# Week_9_8.net
KiCad netlist of a schematic drawn in EAGLE
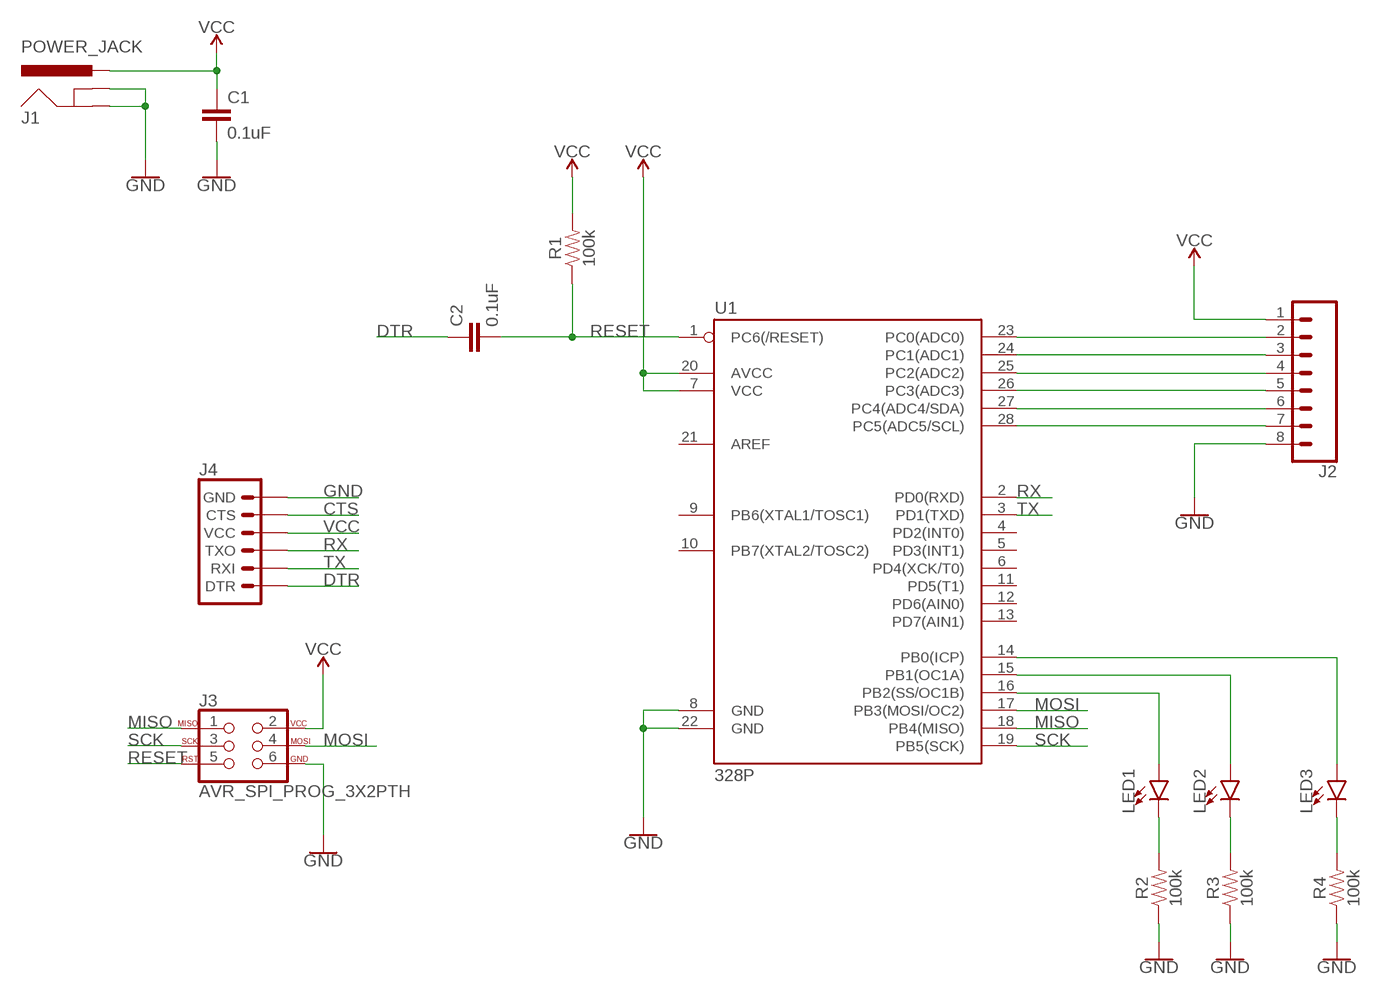
[diagram p0: schematic, sheet 1]

(export (version "E")
  (design (tool "Eeschema 10.0.6"))
  (components
    (comp (ref "C1")
      (value "0.1uF")
      (footprint "eagle-import:CAP-PTH-SMALL-KIT")
      (libsource (lib "eagle-import") (part "0.1UF-KIT-EZ-50V-20%"))
    )
    (comp (ref "C2")
      (value "0.1uF")
      (footprint "eagle-import:CAP-PTH-SMALL-KIT")
      (libsource (lib "eagle-import") (part "0.1UF-KIT-EZ-50V-20%"))
    )
    (comp (ref "J1")
      (value "POWER_JACK")
      (footprint "eagle-import:POWER_JACK_PTH")
      (libsource (lib "eagle-import") (part "POWER_JACK"))
    )
    (comp (ref "J2")
      (value "CONN_08\"")
      (footprint "eagle-import:1X08")
      (libsource (lib "eagle-import") (part "CONN_08{dblquote}"))
    )
    (comp (ref "J3")
      (value "AVR_SPI_PROG_3X2PTH")
      (footprint "eagle-import:2X3")
      (libsource (lib "eagle-import") (part "AVR_SPI_PROG_3X2PTH"))
    )
    (comp (ref "J4")
      (value "6_PIN_SERIAL_TARGET")
      (footprint "eagle-import:1X06")
      (libsource (lib "eagle-import") (part "6_PIN_SERIAL_TARGET"))
    )
    (comp (ref "LED1")
      (value "LED5MM")
      (footprint "eagle-import:LED_5MM")
      (libsource (lib "eagle-import") (part "LED5MM"))
    )
    (comp (ref "LED2")
      (value "LED5MM")
      (footprint "eagle-import:LED_5MM")
      (libsource (lib "eagle-import") (part "LED5MM"))
    )
    (comp (ref "LED3")
      (value "LED5MM")
      (footprint "eagle-import:LED_5MM")
      (libsource (lib "eagle-import") (part "LED5MM"))
    )
    (comp (ref "R1")
      (value "100k")
      (footprint "eagle-import:AXIAL-0.3")
      (libsource (lib "eagle-import") (part "100KOHM-HORIZ-1/4W-1%"))
    )
    (comp (ref "R2")
      (value "100k")
      (footprint "eagle-import:AXIAL-0.3")
      (libsource (lib "eagle-import") (part "100KOHM-HORIZ-1/4W-1%"))
    )
    (comp (ref "R3")
      (value "100k")
      (footprint "eagle-import:AXIAL-0.3")
      (libsource (lib "eagle-import") (part "100KOHM-HORIZ-1/4W-1%"))
    )
    (comp (ref "R4")
      (value "100k")
      (footprint "eagle-import:AXIAL-0.3")
      (libsource (lib "eagle-import") (part "100KOHM-HORIZ-1/4W-1%"))
    )
    (comp (ref "U1")
      (value "328P")
      (footprint "eagle-import:DIP28")
      (libsource (lib "eagle-import") (part "ATMEGA328P_PDIP"))
    )
  )
  (nets
    (net (code "1") (name "/CTS") (class "Default")
      (node (ref "J4") (pin "5") (pinfunction "CTS_5") (pintype "passive"))
    )
    (net (code "2") (name "/DTR") (class "Default")
      (node (ref "C2") (pin "1") (pinfunction "1_1") (pintype "passive"))
      (node (ref "J4") (pin "1") (pinfunction "DTR_1") (pintype "passive"))
    )
    (net (code "3") (name "/MISO") (class "Default")
      (node (ref "J3") (pin "1") (pinfunction "1_1") (pintype "passive"))
      (node (ref "U1") (pin "18") (pinfunction "PB4(MISO)_18") (pintype "bidirectional"))
    )
    (net (code "4") (name "/MOSI") (class "Default")
      (node (ref "J3") (pin "4") (pinfunction "4_4") (pintype "passive"))
      (node (ref "U1") (pin "17") (pinfunction "PB3(MOSI/OC2)_17") (pintype "bidirectional"))
    )
    (net (code "5") (name "/RESET") (class "Default")
      (node (ref "C2") (pin "2") (pinfunction "2_2") (pintype "passive"))
      (node (ref "J3") (pin "5") (pinfunction "5_5") (pintype "passive"))
      (node (ref "R1") (pin "P$1") (pinfunction "1_P$1") (pintype "passive"))
      (node (ref "U1") (pin "1") (pinfunction "PC6(/RESET)_1") (pintype "bidirectional"))
    )
    (net (code "6") (name "/RX") (class "Default")
      (node (ref "J4") (pin "3") (pinfunction "TXO_3") (pintype "passive"))
      (node (ref "U1") (pin "2") (pinfunction "PD0(RXD)_2") (pintype "bidirectional"))
    )
    (net (code "7") (name "/SCK") (class "Default")
      (node (ref "J3") (pin "3") (pinfunction "3_3") (pintype "passive"))
      (node (ref "U1") (pin "19") (pinfunction "PB5(SCK)_19") (pintype "bidirectional"))
    )
    (net (code "8") (name "/TX") (class "Default")
      (node (ref "J4") (pin "2") (pinfunction "RXI_2") (pintype "passive"))
      (node (ref "U1") (pin "3") (pinfunction "PD1(TXD)_3") (pintype "bidirectional"))
    )
    (net (code "9") (name "GND") (class "Default")
      (node (ref "C1") (pin "2") (pinfunction "2_2") (pintype "passive"))
      (node (ref "J1") (pin "GND") (pinfunction "GND_GND") (pintype "bidirectional"))
      (node (ref "J1") (pin "GNDBREAK") (pinfunction "GNDBREAK_GNDBREAK") (pintype "bidirectional"))
      (node (ref "J2") (pin "8") (pinfunction "8_8") (pintype "passive"))
      (node (ref "J3") (pin "6") (pinfunction "6_6") (pintype "passive"))
      (node (ref "J4") (pin "6") (pinfunction "GND_6") (pintype "passive"))
      (node (ref "R2") (pin "P$1") (pinfunction "1_P$1") (pintype "passive"))
      (node (ref "R3") (pin "P$1") (pinfunction "1_P$1") (pintype "passive"))
      (node (ref "R4") (pin "P$1") (pinfunction "1_P$1") (pintype "passive"))
      (node (ref "U1") (pin "22") (pinfunction "GND_22") (pintype "bidirectional"))
      (node (ref "U1") (pin "8") (pinfunction "GND_8") (pintype "bidirectional"))
    )
    (net (code "10") (name "Net-(LED1-C)") (class "Default")
      (node (ref "LED1") (pin "K") (pinfunction "C_K") (pintype "passive"))
      (node (ref "R2") (pin "P$2") (pinfunction "2_P$2") (pintype "passive"))
    )
    (net (code "11") (name "Net-(LED2-C)") (class "Default")
      (node (ref "LED2") (pin "K") (pinfunction "C_K") (pintype "passive"))
      (node (ref "R3") (pin "P$2") (pinfunction "2_P$2") (pintype "passive"))
    )
    (net (code "12") (name "Net-(LED3-C)") (class "Default")
      (node (ref "LED3") (pin "K") (pinfunction "C_K") (pintype "passive"))
      (node (ref "R4") (pin "P$2") (pinfunction "2_P$2") (pintype "passive"))
    )
    (net (code "13") (name "Net-(U1-PB0(ICP))") (class "Default")
      (node (ref "LED3") (pin "A") (pinfunction "A_A") (pintype "passive"))
      (node (ref "U1") (pin "14") (pinfunction "PB0(ICP)_14") (pintype "bidirectional"))
    )
    (net (code "14") (name "Net-(U1-PB1(OC1A))") (class "Default")
      (node (ref "LED2") (pin "A") (pinfunction "A_A") (pintype "passive"))
      (node (ref "U1") (pin "15") (pinfunction "PB1(OC1A)_15") (pintype "bidirectional"))
    )
    (net (code "15") (name "Net-(U1-PB2(SS{slash}OC1B))") (class "Default")
      (node (ref "LED1") (pin "A") (pinfunction "A_A") (pintype "passive"))
      (node (ref "U1") (pin "16") (pinfunction "PB2(SS/OC1B)_16") (pintype "bidirectional"))
    )
    (net (code "16") (name "Net-(U1-PC0(ADC0))") (class "Default")
      (node (ref "J2") (pin "2") (pinfunction "2_2") (pintype "passive"))
      (node (ref "U1") (pin "23") (pinfunction "PC0(ADC0)_23") (pintype "bidirectional"))
    )
    (net (code "17") (name "Net-(U1-PC1(ADC1))") (class "Default")
      (node (ref "J2") (pin "3") (pinfunction "3_3") (pintype "passive"))
      (node (ref "U1") (pin "24") (pinfunction "PC1(ADC1)_24") (pintype "bidirectional"))
    )
    (net (code "18") (name "Net-(U1-PC2(ADC2))") (class "Default")
      (node (ref "J2") (pin "4") (pinfunction "4_4") (pintype "passive"))
      (node (ref "U1") (pin "25") (pinfunction "PC2(ADC2)_25") (pintype "bidirectional"))
    )
    (net (code "19") (name "Net-(U1-PC3(ADC3))") (class "Default")
      (node (ref "J2") (pin "5") (pinfunction "5_5") (pintype "passive"))
      (node (ref "U1") (pin "26") (pinfunction "PC3(ADC3)_26") (pintype "bidirectional"))
    )
    (net (code "20") (name "Net-(U1-PC4(ADC4{slash}SDA))") (class "Default")
      (node (ref "J2") (pin "6") (pinfunction "6_6") (pintype "passive"))
      (node (ref "U1") (pin "27") (pinfunction "PC4(ADC4/SDA)_27") (pintype "bidirectional"))
    )
    (net (code "21") (name "Net-(U1-PC5(ADC5{slash}SCL))") (class "Default")
      (node (ref "J2") (pin "7") (pinfunction "7_7") (pintype "passive"))
      (node (ref "U1") (pin "28") (pinfunction "PC5(ADC5/SCL)_28") (pintype "bidirectional"))
    )
    (net (code "22") (name "VCC") (class "Default")
      (node (ref "C1") (pin "1") (pinfunction "1_1") (pintype "passive"))
      (node (ref "J1") (pin "PWR") (pinfunction "PWR_PWR") (pintype "bidirectional"))
      (node (ref "J2") (pin "1") (pinfunction "1_1") (pintype "passive"))
      (node (ref "J3") (pin "2") (pinfunction "2_2") (pintype "passive"))
      (node (ref "J4") (pin "4") (pinfunction "VCC_4") (pintype "passive"))
      (node (ref "R1") (pin "P$2") (pinfunction "2_P$2") (pintype "passive"))
      (node (ref "U1") (pin "20") (pinfunction "AVCC_20") (pintype "bidirectional"))
      (node (ref "U1") (pin "7") (pinfunction "VCC_7") (pintype "bidirectional"))
    )
    (net (code "23") (name "unconnected-(U1-AREF-Pad21)") (class "Default")
      (node (ref "U1") (pin "21") (pinfunction "AREF_21") (pintype "bidirectional"))
    )
    (net (code "24") (name "unconnected-(U1-PB6(XTAL1{slash}TOSC1)-Pad9)") (class "Default")
      (node (ref "U1") (pin "9") (pinfunction "PB6(XTAL1/TOSC1)_9") (pintype "bidirectional"))
    )
    (net (code "25") (name "unconnected-(U1-PB7(XTAL2{slash}TOSC2)-Pad10)") (class "Default")
      (node (ref "U1") (pin "10") (pinfunction "PB7(XTAL2/TOSC2)_10") (pintype "bidirectional"))
    )
    (net (code "26") (name "unconnected-(U1-PD2(INT0)-Pad4)") (class "Default")
      (node (ref "U1") (pin "4") (pinfunction "PD2(INT0)_4") (pintype "bidirectional"))
    )
    (net (code "27") (name "unconnected-(U1-PD3(INT1)-Pad5)") (class "Default")
      (node (ref "U1") (pin "5") (pinfunction "PD3(INT1)_5") (pintype "bidirectional"))
    )
    (net (code "28") (name "unconnected-(U1-PD4(XCK{slash}T0)-Pad6)") (class "Default")
      (node (ref "U1") (pin "6") (pinfunction "PD4(XCK/T0)_6") (pintype "bidirectional"))
    )
    (net (code "29") (name "unconnected-(U1-PD5(T1)-Pad11)") (class "Default")
      (node (ref "U1") (pin "11") (pinfunction "PD5(T1)_11") (pintype "bidirectional"))
    )
    (net (code "30") (name "unconnected-(U1-PD6(AIN0)-Pad12)") (class "Default")
      (node (ref "U1") (pin "12") (pinfunction "PD6(AIN0)_12") (pintype "bidirectional"))
    )
    (net (code "31") (name "unconnected-(U1-PD7(AIN1)-Pad13)") (class "Default")
      (node (ref "U1") (pin "13") (pinfunction "PD7(AIN1)_13") (pintype "bidirectional"))
    )
  )
)
